# DAC_buffer_non-inv.net
KiCad netlist of a schematic drawn in EAGLE
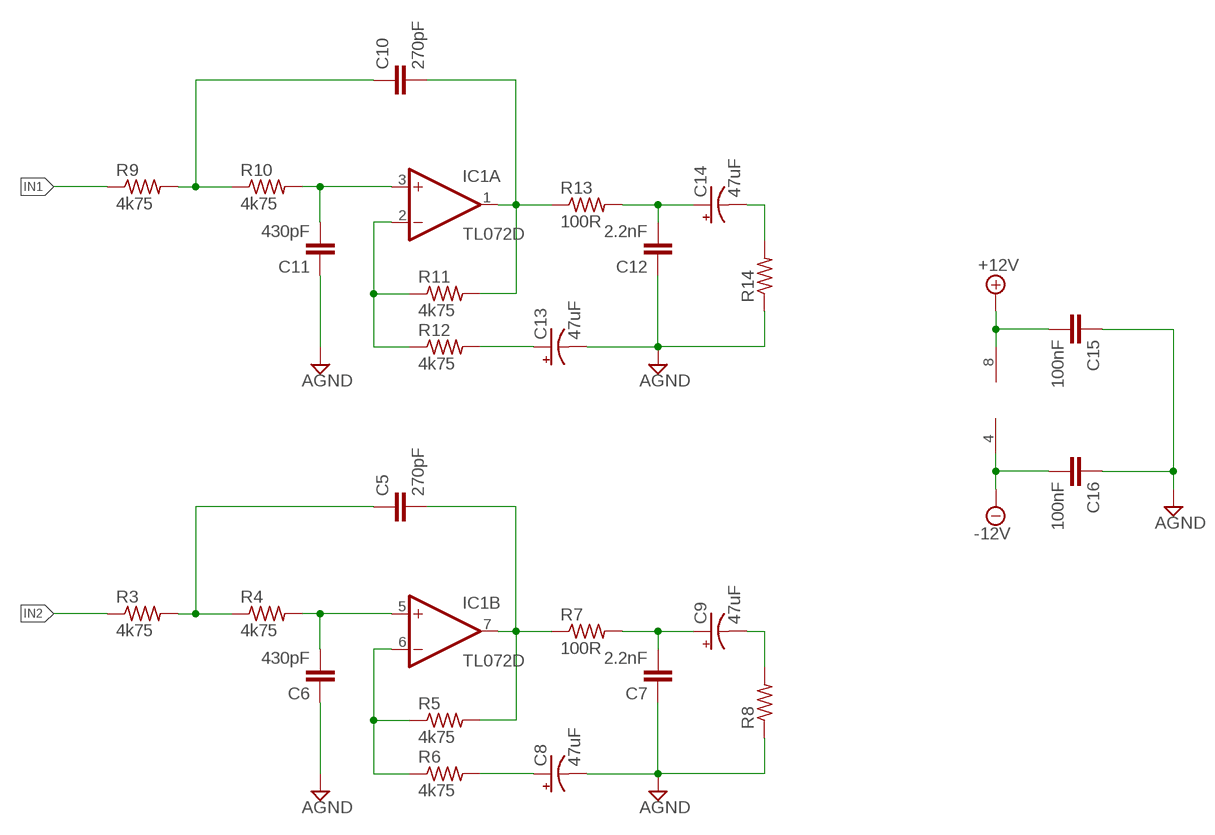
[diagram p0: schematic, sheet 1]

(export (version "E")
  (design (tool "Eeschema 10.0.6"))
  (components
    (comp (ref "C5")
      (value "270pF")
      (footprint "eagle-import:C0603")
      (libsource (lib "eagle-import") (part "C-EUC0603"))
    )
    (comp (ref "C6")
      (value "430pF")
      (footprint "eagle-import:C0603")
      (libsource (lib "eagle-import") (part "C-EUC0603"))
    )
    (comp (ref "C7")
      (value "2.2nF")
      (footprint "eagle-import:C0603")
      (libsource (lib "eagle-import") (part "C-EUC0603"))
    )
    (comp (ref "C8")
      (value "47uF")
      (footprint "eagle-import:PANASONIC_A")
      (libsource (lib "eagle-import") (part "CPOL-USA"))
    )
    (comp (ref "C9")
      (value "47uF")
      (footprint "eagle-import:PANASONIC_A")
      (libsource (lib "eagle-import") (part "CPOL-USA"))
    )
    (comp (ref "C10")
      (value "270pF")
      (footprint "eagle-import:C0603")
      (libsource (lib "eagle-import") (part "C-EUC0603"))
    )
    (comp (ref "C11")
      (value "430pF")
      (footprint "eagle-import:C0603")
      (libsource (lib "eagle-import") (part "C-EUC0603"))
    )
    (comp (ref "C12")
      (value "2.2nF")
      (footprint "eagle-import:C0603")
      (libsource (lib "eagle-import") (part "C-EUC0603"))
    )
    (comp (ref "C13")
      (value "47uF")
      (footprint "eagle-import:PANASONIC_A")
      (libsource (lib "eagle-import") (part "CPOL-USA"))
    )
    (comp (ref "C14")
      (value "47uF")
      (footprint "eagle-import:PANASONIC_A")
      (libsource (lib "eagle-import") (part "CPOL-USA"))
    )
    (comp (ref "C15")
      (value "100nF")
      (footprint "eagle-import:C0603")
      (libsource (lib "eagle-import") (part "C-EUC0603"))
    )
    (comp (ref "C16")
      (value "100nF")
      (footprint "eagle-import:C0603")
      (libsource (lib "eagle-import") (part "C-EUC0603"))
    )
    (comp (ref "IC1")
      (value "TL072D")
      (footprint "eagle-import:SO08")
      (libsource (lib "eagle-import") (part "TL072D"))
    )
    (comp (ref "R3")
      (value "4k75")
      (footprint "eagle-import:R0603")
      (libsource (lib "eagle-import") (part "R-US_R0603"))
    )
    (comp (ref "R4")
      (value "4k75")
      (footprint "eagle-import:R0603")
      (libsource (lib "eagle-import") (part "R-US_R0603"))
    )
    (comp (ref "R5")
      (value "4k75")
      (footprint "eagle-import:R0603")
      (libsource (lib "eagle-import") (part "R-US_R0603"))
    )
    (comp (ref "R6")
      (value "4k75")
      (footprint "eagle-import:R0603")
      (libsource (lib "eagle-import") (part "R-US_R0603"))
    )
    (comp (ref "R7")
      (value "100R")
      (footprint "eagle-import:R0603")
      (libsource (lib "eagle-import") (part "R-US_R0603"))
    )
    (comp (ref "R8")
      (value "R-US_R0603")
      (footprint "eagle-import:R0603")
      (libsource (lib "eagle-import") (part "R-US_R0603"))
    )
    (comp (ref "R9")
      (value "4k75")
      (footprint "eagle-import:R0603")
      (libsource (lib "eagle-import") (part "R-US_R0603"))
    )
    (comp (ref "R10")
      (value "4k75")
      (footprint "eagle-import:R0603")
      (libsource (lib "eagle-import") (part "R-US_R0603"))
    )
    (comp (ref "R11")
      (value "4k75")
      (footprint "eagle-import:R0603")
      (libsource (lib "eagle-import") (part "R-US_R0603"))
    )
    (comp (ref "R12")
      (value "4k75")
      (footprint "eagle-import:R0603")
      (libsource (lib "eagle-import") (part "R-US_R0603"))
    )
    (comp (ref "R13")
      (value "100R")
      (footprint "eagle-import:R0603")
      (libsource (lib "eagle-import") (part "R-US_R0603"))
    )
    (comp (ref "R14")
      (value "R-US_R0603")
      (footprint "eagle-import:R0603")
      (libsource (lib "eagle-import") (part "R-US_R0603"))
    )
  )
  (nets
    (net (code "1") (name "+12V") (class "Default")
      (node (ref "C15") (pin "2") (pinfunction "2_2") (pintype "passive"))
      (node (ref "IC1") (pin "8") (pinfunction "V+_8") (pintype "power_in"))
    )
    (net (code "2") (name "-12V") (class "Default")
      (node (ref "C16") (pin "2") (pinfunction "2_2") (pintype "passive"))
      (node (ref "IC1") (pin "4") (pinfunction "V-_4") (pintype "power_in"))
    )
    (net (code "3") (name "AGND") (class "Default")
      (node (ref "C11") (pin "1") (pinfunction "1_1") (pintype "passive"))
      (node (ref "C12") (pin "1") (pinfunction "1_1") (pintype "passive"))
      (node (ref "C13") (pin "-") (pinfunction "-_-") (pintype "passive"))
      (node (ref "C15") (pin "1") (pinfunction "1_1") (pintype "passive"))
      (node (ref "C16") (pin "1") (pinfunction "1_1") (pintype "passive"))
      (node (ref "C6") (pin "1") (pinfunction "1_1") (pintype "passive"))
      (node (ref "C7") (pin "1") (pinfunction "1_1") (pintype "passive"))
      (node (ref "C8") (pin "-") (pinfunction "-_-") (pintype "passive"))
      (node (ref "R14") (pin "1") (pinfunction "1_1") (pintype "passive"))
      (node (ref "R8") (pin "1") (pinfunction "1_1") (pintype "passive"))
    )
    (net (code "4") (name "IN1") (class "Default")
      (node (ref "R9") (pin "1") (pinfunction "1_1") (pintype "passive"))
    )
    (net (code "5") (name "IN2") (class "Default")
      (node (ref "R3") (pin "1") (pinfunction "1_1") (pintype "passive"))
    )
    (net (code "6") (name "Net-(C5-Pad1)") (class "Default")
      (node (ref "C5") (pin "1") (pinfunction "1_1") (pintype "passive"))
      (node (ref "R3") (pin "2") (pinfunction "2_2") (pintype "passive"))
      (node (ref "R4") (pin "1") (pinfunction "1_1") (pintype "passive"))
    )
    (net (code "7") (name "Net-(C7-Pad2)") (class "Default")
      (node (ref "C7") (pin "2") (pinfunction "2_2") (pintype "passive"))
      (node (ref "C9") (pin "+") (pinfunction "+_+") (pintype "passive"))
      (node (ref "R7") (pin "2") (pinfunction "2_2") (pintype "passive"))
    )
    (net (code "8") (name "Net-(C8-Pad+)") (class "Default")
      (node (ref "C8") (pin "+") (pinfunction "+_+") (pintype "passive"))
      (node (ref "R6") (pin "2") (pinfunction "2_2") (pintype "passive"))
    )
    (net (code "9") (name "Net-(C9-Pad-)") (class "Default")
      (node (ref "C9") (pin "-") (pinfunction "-_-") (pintype "passive"))
      (node (ref "R8") (pin "2") (pinfunction "2_2") (pintype "passive"))
    )
    (net (code "10") (name "Net-(C10-Pad1)") (class "Default")
      (node (ref "C10") (pin "1") (pinfunction "1_1") (pintype "passive"))
      (node (ref "R10") (pin "1") (pinfunction "1_1") (pintype "passive"))
      (node (ref "R9") (pin "2") (pinfunction "2_2") (pintype "passive"))
    )
    (net (code "11") (name "Net-(C12-Pad2)") (class "Default")
      (node (ref "C12") (pin "2") (pinfunction "2_2") (pintype "passive"))
      (node (ref "C14") (pin "+") (pinfunction "+_+") (pintype "passive"))
      (node (ref "R13") (pin "2") (pinfunction "2_2") (pintype "passive"))
    )
    (net (code "12") (name "Net-(C13-Pad+)") (class "Default")
      (node (ref "C13") (pin "+") (pinfunction "+_+") (pintype "passive"))
      (node (ref "R12") (pin "2") (pinfunction "2_2") (pintype "passive"))
    )
    (net (code "13") (name "Net-(C14-Pad-)") (class "Default")
      (node (ref "C14") (pin "-") (pinfunction "-_-") (pintype "passive"))
      (node (ref "R14") (pin "2") (pinfunction "2_2") (pintype "passive"))
    )
    (net (code "14") (name "Net-(IC1A-+IN)") (class "Default")
      (node (ref "C11") (pin "2") (pinfunction "2_2") (pintype "passive"))
      (node (ref "IC1") (pin "3") (pinfunction "+IN_3") (pintype "input"))
      (node (ref "R10") (pin "2") (pinfunction "2_2") (pintype "passive"))
    )
    (net (code "15") (name "Net-(IC1A--IN)") (class "Default")
      (node (ref "IC1") (pin "2") (pinfunction "-IN_2") (pintype "input"))
      (node (ref "R11") (pin "1") (pinfunction "1_1") (pintype "passive"))
      (node (ref "R12") (pin "1") (pinfunction "1_1") (pintype "passive"))
    )
    (net (code "16") (name "Net-(IC1A-OUT)") (class "Default")
      (node (ref "C10") (pin "2") (pinfunction "2_2") (pintype "passive"))
      (node (ref "IC1") (pin "1") (pinfunction "OUT_1") (pintype "output"))
      (node (ref "R11") (pin "2") (pinfunction "2_2") (pintype "passive"))
      (node (ref "R13") (pin "1") (pinfunction "1_1") (pintype "passive"))
    )
    (net (code "17") (name "Net-(IC1B-+IN)") (class "Default")
      (node (ref "C6") (pin "2") (pinfunction "2_2") (pintype "passive"))
      (node (ref "IC1") (pin "5") (pinfunction "+IN_5") (pintype "input"))
      (node (ref "R4") (pin "2") (pinfunction "2_2") (pintype "passive"))
    )
    (net (code "18") (name "Net-(IC1B--IN)") (class "Default")
      (node (ref "IC1") (pin "6") (pinfunction "-IN_6") (pintype "input"))
      (node (ref "R5") (pin "1") (pinfunction "1_1") (pintype "passive"))
      (node (ref "R6") (pin "1") (pinfunction "1_1") (pintype "passive"))
    )
    (net (code "19") (name "Net-(IC1B-OUT)") (class "Default")
      (node (ref "C5") (pin "2") (pinfunction "2_2") (pintype "passive"))
      (node (ref "IC1") (pin "7") (pinfunction "OUT_7") (pintype "output"))
      (node (ref "R5") (pin "2") (pinfunction "2_2") (pintype "passive"))
      (node (ref "R7") (pin "1") (pinfunction "1_1") (pintype "passive"))
    )
  )
)
